# Rev_B.net
KiCad netlist of a schematic drawn in EAGLE
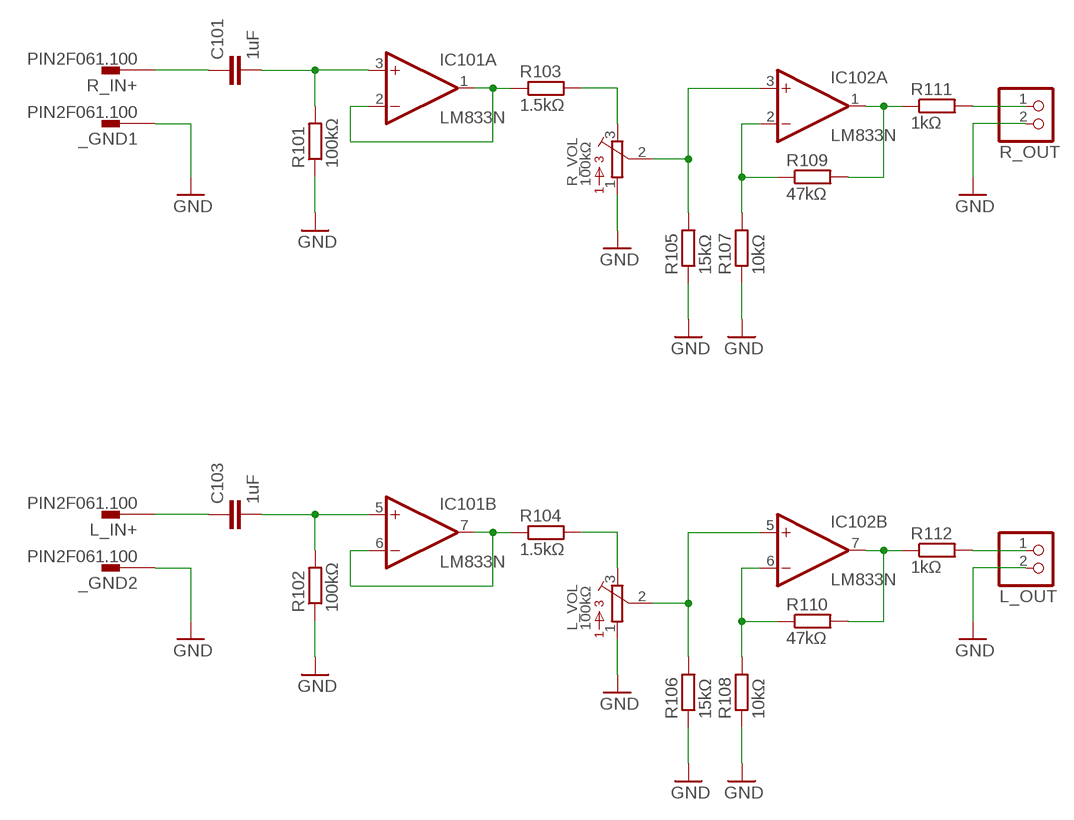
[diagram p0: schematic, sheet 1]
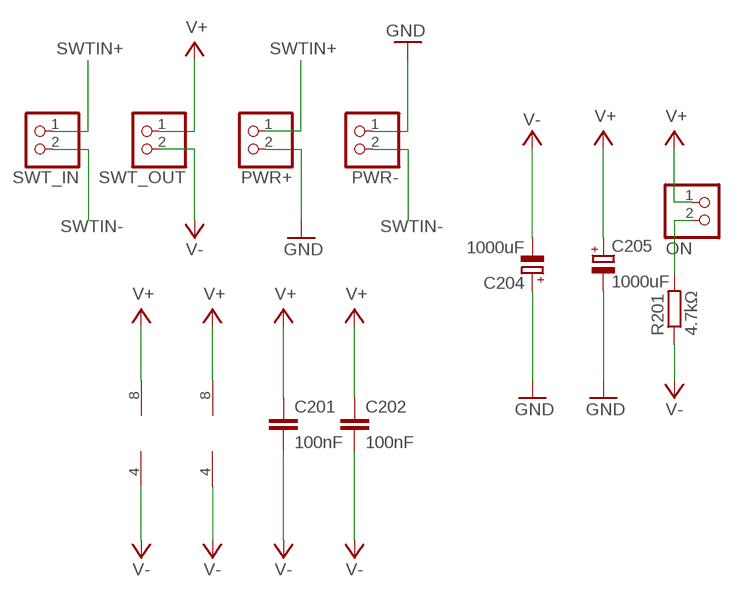
[diagram p1: schematic, sheet 2]

(export (version "E")
  (design (tool "Eeschema 10.0.6"))
  (components
    (comp (ref "C201")
      (value "100nF")
      (footprint "eagle-import:C025-025X050")
      (libsource (lib "eagle-import") (part "C-EU025-025X050"))
    )
    (comp (ref "C202")
      (value "100nF")
      (footprint "eagle-import:C025-025X050")
      (libsource (lib "eagle-import") (part "C-EU025-025X050"))
    )
    (comp (ref "C204")
      (value "1000uF")
      (footprint "eagle-import:E5-10,5")
      (libsource (lib "eagle-import") (part "CPOL-EUE5-10.5"))
    )
    (comp (ref "C205")
      (value "1000uF")
      (footprint "eagle-import:E5-10,5")
      (libsource (lib "eagle-import") (part "CPOL-EUE5-10.5"))
    )
    (comp (ref "IC101")
      (value "LM833N")
      (footprint "eagle-import:DIL08")
      (libsource (lib "eagle-import") (part "LM833N"))
    )
    (comp (ref "IC102")
      (value "LM833N")
      (footprint "eagle-import:DIL08")
      (libsource (lib "eagle-import") (part "LM833N"))
    )
    (comp (ref "ON")
      (value "JST_2PIN-THM")
      (footprint "eagle-import:JST-PH-2-THM")
      (libsource (lib "eagle-import") (part "JST_2PIN-THM"))
    )
    (comp (ref "PWR+")
      (value "JST_2PIN-THM")
      (footprint "eagle-import:JST-PH-2-THM")
      (libsource (lib "eagle-import") (part "JST_2PIN-THM"))
    )
    (comp (ref "PWR-")
      (value "JST_2PIN-THM")
      (footprint "eagle-import:JST-PH-2-THM")
      (libsource (lib "eagle-import") (part "JST_2PIN-THM"))
    )
    (comp (ref "R201")
      (value "4.7kΩ")
      (footprint "eagle-import:0207_10")
      (libsource (lib "eagle-import") (part "R-EU_0207/10"))
    )
    (comp (ref "SWT_IN")
      (value "JST_2PIN-THM")
      (footprint "eagle-import:JST-PH-2-THM")
      (libsource (lib "eagle-import") (part "JST_2PIN-THM"))
    )
    (comp (ref "SWT_OUT")
      (value "JST_2PIN-THM")
      (footprint "eagle-import:JST-PH-2-THM")
      (libsource (lib "eagle-import") (part "JST_2PIN-THM"))
    )
    (comp (ref "C101")
      (value "1uF")
      (footprint "eagle-import:C150-072X183")
      (libsource (lib "eagle-import") (part "C-EU150-072X183"))
    )
    (comp (ref "C103")
      (value "1uF")
      (footprint "eagle-import:C150-072X183")
      (libsource (lib "eagle-import") (part "C-EU150-072X183"))
    )
    (comp (ref "L_IN+")
      (value "PIN2F061.100")
      (footprint "eagle-import:F061.100")
      (libsource (lib "eagle-import") (part "PIN2F061.100"))
    )
    (comp (ref "L_OUT")
      (value "JST_2PIN-THM")
      (footprint "eagle-import:JST-PH-2-THM")
      (libsource (lib "eagle-import") (part "JST_2PIN-THM"))
    )
    (comp (ref "L_VOL")
      (value "100kΩ")
      (footprint "eagle-import:3362U")
      (libsource (lib "eagle-import") (part "3362U"))
    )
    (comp (ref "R101")
      (value "100kΩ")
      (footprint "eagle-import:0207_10")
      (libsource (lib "eagle-import") (part "R-EU_0207/10"))
    )
    (comp (ref "R102")
      (value "100kΩ")
      (footprint "eagle-import:0207_10")
      (libsource (lib "eagle-import") (part "R-EU_0207/10"))
    )
    (comp (ref "R103")
      (value "1.5kΩ")
      (footprint "eagle-import:0207_10")
      (libsource (lib "eagle-import") (part "R-EU_0207/10"))
    )
    (comp (ref "R104")
      (value "1.5kΩ")
      (footprint "eagle-import:0207_10")
      (libsource (lib "eagle-import") (part "R-EU_0207/10"))
    )
    (comp (ref "R105")
      (value "15kΩ")
      (footprint "eagle-import:0207_10")
      (libsource (lib "eagle-import") (part "R-EU_0207/10"))
    )
    (comp (ref "R106")
      (value "15kΩ")
      (footprint "eagle-import:0207_10")
      (libsource (lib "eagle-import") (part "R-EU_0207/10"))
    )
    (comp (ref "R107")
      (value "10kΩ")
      (footprint "eagle-import:0207_10")
      (libsource (lib "eagle-import") (part "R-EU_0207/10"))
    )
    (comp (ref "R108")
      (value "10kΩ")
      (footprint "eagle-import:0207_10")
      (libsource (lib "eagle-import") (part "R-EU_0207/10"))
    )
    (comp (ref "R109")
      (value "47kΩ")
      (footprint "eagle-import:0207_10")
      (libsource (lib "eagle-import") (part "R-EU_0207/10"))
    )
    (comp (ref "R110")
      (value "47kΩ")
      (footprint "eagle-import:0207_10")
      (libsource (lib "eagle-import") (part "R-EU_0207/10"))
    )
    (comp (ref "R111")
      (value "1kΩ")
      (footprint "eagle-import:0207_10")
      (libsource (lib "eagle-import") (part "R-EU_0207/10"))
    )
    (comp (ref "R112")
      (value "1kΩ")
      (footprint "eagle-import:0207_10")
      (libsource (lib "eagle-import") (part "R-EU_0207/10"))
    )
    (comp (ref "R_IN+")
      (value "PIN2F061.100")
      (footprint "eagle-import:F061.100")
      (libsource (lib "eagle-import") (part "PIN2F061.100"))
    )
    (comp (ref "R_OUT")
      (value "JST_2PIN-THM")
      (footprint "eagle-import:JST-PH-2-THM")
      (libsource (lib "eagle-import") (part "JST_2PIN-THM"))
    )
    (comp (ref "R_VOL")
      (value "100kΩ")
      (footprint "eagle-import:3362U")
      (libsource (lib "eagle-import") (part "3362U"))
    )
    (comp (ref "_GND1")
      (value "PIN2F061.100")
      (footprint "eagle-import:F061.100")
      (libsource (lib "eagle-import") (part "PIN2F061.100"))
    )
    (comp (ref "_GND2")
      (value "PIN2F061.100")
      (footprint "eagle-import:F061.100")
      (libsource (lib "eagle-import") (part "PIN2F061.100"))
    )
  )
  (nets
    (net (code "1") (name "GND") (class "Default")
      (node (ref "C204") (pin "+") (pinfunction "+_+") (pintype "passive"))
      (node (ref "C205") (pin "-") (pinfunction "-_-") (pintype "passive"))
      (node (ref "L_OUT") (pin "2") (pinfunction "1_2") (pintype "passive"))
      (node (ref "L_VOL") (pin "1") (pinfunction "1_1") (pintype "passive"))
      (node (ref "PWR+") (pin "2") (pinfunction "1_2") (pintype "passive"))
      (node (ref "PWR-") (pin "1") (pinfunction "2_1") (pintype "passive"))
      (node (ref "R101") (pin "1") (pinfunction "1_1") (pintype "passive"))
      (node (ref "R102") (pin "1") (pinfunction "1_1") (pintype "passive"))
      (node (ref "R105") (pin "1") (pinfunction "1_1") (pintype "passive"))
      (node (ref "R106") (pin "1") (pinfunction "1_1") (pintype "passive"))
      (node (ref "R107") (pin "1") (pinfunction "1_1") (pintype "passive"))
      (node (ref "R108") (pin "1") (pinfunction "1_1") (pintype "passive"))
      (node (ref "R_OUT") (pin "2") (pinfunction "1_2") (pintype "passive"))
      (node (ref "R_VOL") (pin "1") (pinfunction "1_1") (pintype "passive"))
      (node (ref "_GND1") (pin "A1") (pinfunction "1_A1") (pintype "passive"))
      (node (ref "_GND1") (pin "A2") (pinfunction "1_A2") (pintype "passive"))
      (node (ref "_GND2") (pin "A1") (pinfunction "1_A1") (pintype "passive"))
      (node (ref "_GND2") (pin "A2") (pinfunction "1_A2") (pintype "passive"))
    )
    (net (code "2") (name "Net-(C101-Pad1)") (class "Default")
      (node (ref "C101") (pin "1") (pinfunction "1_1") (pintype "passive"))
      (node (ref "R_IN+") (pin "A1") (pinfunction "1_A1") (pintype "passive"))
      (node (ref "R_IN+") (pin "A2") (pinfunction "1_A2") (pintype "passive"))
    )
    (net (code "3") (name "Net-(C103-Pad1)") (class "Default")
      (node (ref "C103") (pin "1") (pinfunction "1_1") (pintype "passive"))
      (node (ref "L_IN+") (pin "A1") (pinfunction "1_A1") (pintype "passive"))
      (node (ref "L_IN+") (pin "A2") (pinfunction "1_A2") (pintype "passive"))
    )
    (net (code "4") (name "Net-(IC101A-+IN)") (class "Default")
      (node (ref "C101") (pin "2") (pinfunction "2_2") (pintype "passive"))
      (node (ref "IC101") (pin "3") (pinfunction "+IN_3") (pintype "input"))
      (node (ref "R101") (pin "2") (pinfunction "2_2") (pintype "passive"))
    )
    (net (code "5") (name "Net-(IC101A--IN)") (class "Default")
      (node (ref "IC101") (pin "1") (pinfunction "OUT_1") (pintype "output"))
      (node (ref "IC101") (pin "2") (pinfunction "-IN_2") (pintype "input"))
      (node (ref "R103") (pin "1") (pinfunction "1_1") (pintype "passive"))
    )
    (net (code "6") (name "Net-(IC101B-+IN)") (class "Default")
      (node (ref "C103") (pin "2") (pinfunction "2_2") (pintype "passive"))
      (node (ref "IC101") (pin "5") (pinfunction "+IN_5") (pintype "input"))
      (node (ref "R102") (pin "2") (pinfunction "2_2") (pintype "passive"))
    )
    (net (code "7") (name "Net-(IC101B--IN)") (class "Default")
      (node (ref "IC101") (pin "6") (pinfunction "-IN_6") (pintype "input"))
      (node (ref "IC101") (pin "7") (pinfunction "OUT_7") (pintype "output"))
      (node (ref "R104") (pin "1") (pinfunction "1_1") (pintype "passive"))
    )
    (net (code "8") (name "Net-(IC102A-+IN)") (class "Default")
      (node (ref "IC102") (pin "3") (pinfunction "+IN_3") (pintype "input"))
      (node (ref "R105") (pin "2") (pinfunction "2_2") (pintype "passive"))
      (node (ref "R_VOL") (pin "2") (pinfunction "2_2") (pintype "passive"))
    )
    (net (code "9") (name "Net-(IC102A--IN)") (class "Default")
      (node (ref "IC102") (pin "2") (pinfunction "-IN_2") (pintype "input"))
      (node (ref "R107") (pin "2") (pinfunction "2_2") (pintype "passive"))
      (node (ref "R109") (pin "1") (pinfunction "1_1") (pintype "passive"))
    )
    (net (code "10") (name "Net-(IC102A-OUT)") (class "Default")
      (node (ref "IC102") (pin "1") (pinfunction "OUT_1") (pintype "output"))
      (node (ref "R109") (pin "2") (pinfunction "2_2") (pintype "passive"))
      (node (ref "R111") (pin "1") (pinfunction "1_1") (pintype "passive"))
    )
    (net (code "11") (name "Net-(IC102B-+IN)") (class "Default")
      (node (ref "IC102") (pin "5") (pinfunction "+IN_5") (pintype "input"))
      (node (ref "L_VOL") (pin "2") (pinfunction "2_2") (pintype "passive"))
      (node (ref "R106") (pin "2") (pinfunction "2_2") (pintype "passive"))
    )
    (net (code "12") (name "Net-(IC102B--IN)") (class "Default")
      (node (ref "IC102") (pin "6") (pinfunction "-IN_6") (pintype "input"))
      (node (ref "R108") (pin "2") (pinfunction "2_2") (pintype "passive"))
      (node (ref "R110") (pin "1") (pinfunction "1_1") (pintype "passive"))
    )
    (net (code "13") (name "Net-(IC102B-OUT)") (class "Default")
      (node (ref "IC102") (pin "7") (pinfunction "OUT_7") (pintype "output"))
      (node (ref "R110") (pin "2") (pinfunction "2_2") (pintype "passive"))
      (node (ref "R112") (pin "1") (pinfunction "1_1") (pintype "passive"))
    )
    (net (code "14") (name "Net-(L_OUT-2)") (class "Default")
      (node (ref "L_OUT") (pin "1") (pinfunction "2_1") (pintype "passive"))
      (node (ref "R112") (pin "2") (pinfunction "2_2") (pintype "passive"))
    )
    (net (code "15") (name "Net-(L_VOL-Pad3)") (class "Default")
      (node (ref "L_VOL") (pin "3") (pinfunction "3_3") (pintype "passive"))
      (node (ref "R104") (pin "2") (pinfunction "2_2") (pintype "passive"))
    )
    (net (code "16") (name "Net-(ON-1)") (class "Default")
      (node (ref "ON") (pin "2") (pinfunction "1_2") (pintype "passive"))
      (node (ref "R201") (pin "2") (pinfunction "2_2") (pintype "passive"))
    )
    (net (code "17") (name "Net-(R103-Pad2)") (class "Default")
      (node (ref "R103") (pin "2") (pinfunction "2_2") (pintype "passive"))
      (node (ref "R_VOL") (pin "3") (pinfunction "3_3") (pintype "passive"))
    )
    (net (code "18") (name "Net-(R_OUT-2)") (class "Default")
      (node (ref "R111") (pin "2") (pinfunction "2_2") (pintype "passive"))
      (node (ref "R_OUT") (pin "1") (pinfunction "2_1") (pintype "passive"))
    )
    (net (code "19") (name "SWTIN+") (class "Default")
      (node (ref "PWR+") (pin "1") (pinfunction "2_1") (pintype "passive"))
      (node (ref "SWT_IN") (pin "1") (pinfunction "2_1") (pintype "passive"))
    )
    (net (code "20") (name "SWTIN-") (class "Default")
      (node (ref "PWR-") (pin "2") (pinfunction "1_2") (pintype "passive"))
      (node (ref "SWT_IN") (pin "2") (pinfunction "1_2") (pintype "passive"))
    )
    (net (code "21") (name "V+") (class "Default")
      (node (ref "C201") (pin "1") (pinfunction "1_1") (pintype "passive"))
      (node (ref "C202") (pin "1") (pinfunction "1_1") (pintype "passive"))
      (node (ref "C205") (pin "+") (pinfunction "+_+") (pintype "passive"))
      (node (ref "IC101") (pin "8") (pinfunction "V+_8") (pintype "power_in"))
      (node (ref "IC102") (pin "8") (pinfunction "V+_8") (pintype "power_in"))
      (node (ref "ON") (pin "1") (pinfunction "2_1") (pintype "passive"))
      (node (ref "SWT_OUT") (pin "1") (pinfunction "2_1") (pintype "passive"))
    )
    (net (code "22") (name "V-") (class "Default")
      (node (ref "C201") (pin "2") (pinfunction "2_2") (pintype "passive"))
      (node (ref "C202") (pin "2") (pinfunction "2_2") (pintype "passive"))
      (node (ref "C204") (pin "-") (pinfunction "-_-") (pintype "passive"))
      (node (ref "IC101") (pin "4") (pinfunction "V-_4") (pintype "power_in"))
      (node (ref "IC102") (pin "4") (pinfunction "V-_4") (pintype "power_in"))
      (node (ref "R201") (pin "1") (pinfunction "1_1") (pintype "passive"))
      (node (ref "SWT_OUT") (pin "2") (pinfunction "1_2") (pintype "passive"))
    )
  )
)
